# encoder.net
KiCad netlist of a schematic drawn in Altium Designer
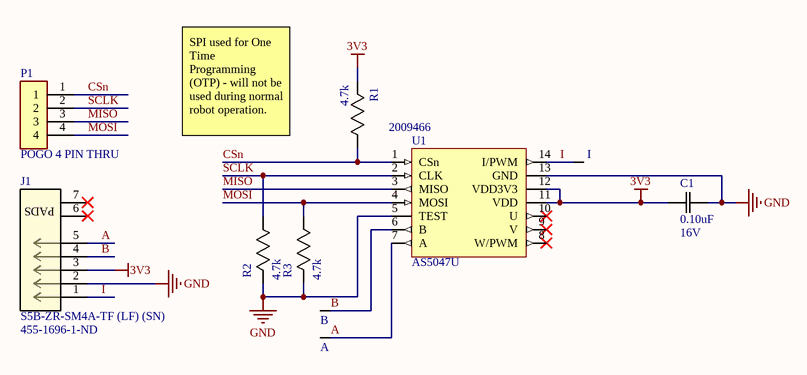
[diagram p0: encoder.SchDoc]

(export (version "E")
  (design (tool "Eeschema 10.0.6"))
  (components
    (comp (ref "A")
      (value "Test Point (Via)")
      (footprint "TP")
      (libsource (lib "AltiumLibraries") (part "Test Point (Via)"))
    )
    (comp (ref "B")
      (value "Test Point (Via)")
      (footprint "TP")
      (libsource (lib "AltiumLibraries") (part "Test Point (Via)"))
    )
    (comp (ref "C1")
      (value "0.10uF")
      (footprint "0603")
      (description "CAP CER 0.10UF 16V X5R 0603/0805")
      (fields (field (name "TOLERANCE") "10%") (field (name "RATING") "16V"))
      (libsource (lib "AltiumLibraries") (part "CAP 0.10uF 16V"))
    )
    (comp (ref "I")
      (value "Test Point (Via)")
      (footprint "TP")
      (libsource (lib "AltiumLibraries") (part "Test Point (Via)"))
    )
    (comp (ref "J1")
      (value "S5B-ZR-SM4A-TF (LF) (SN)")
      (footprint "JST_S5B-ZR-SM4A-TF")
      (description "Connector Header Surface Mount, Right Angle 5 position 0.059\" (1.50mm)")
      (fields
        (field (name "SUPPLIER PART NUMBER 1") "455-1696-1-ND")
        (field (name "COPYRIGHT") "Copyright (C) 2021 Ultra Librarian. All rights reserved.")
      )
      (libsource (lib "AltiumLibraries") (part "CN 5POS JST ZR RA"))
    )
    (comp (ref "P1")
      (value "POGO 4 PIN THRU")
      (footprint "POGO 4 PIN THRU")
      (description "4 pin POGO Holes 0.100\" Pitch")
      (libsource (lib "AltiumLibraries") (part "POGO 4 PIN THRU"))
    )
    (comp (ref "R1")
      (value "4.7k")
      (footprint "0603")
      (description "RES SMD 4.7k OHM 5% 1/8W 0805")
      (fields (field (name "TOLERANCE") "5%"))
      (libsource (lib "AltiumLibraries") (part "RES 4.7k 1/8W - 5%"))
    )
    (comp (ref "R2")
      (value "4.7k")
      (footprint "0603")
      (description "RES SMD 4.7k OHM 5% 1/8W 0805")
      (fields (field (name "TOLERANCE") "5%"))
      (libsource (lib "AltiumLibraries") (part "RES 4.7k 1/8W - 5%"))
    )
    (comp (ref "R3")
      (value "4.7k")
      (footprint "0603")
      (description "RES SMD 4.7k OHM 5% 1/8W 0805")
      (fields (field (name "TOLERANCE") "5%"))
      (libsource (lib "") (part "RES 4.7k 1/8W - 5%_1"))
    )
    (comp (ref "U1")
      (value "AS5047U")
      (footprint "AS5047U")
      (description "14-Bit On-Axis Magnetic Rotary Position Sensor with Up to 14-Bit Binary Incremental Pulse Count")
      (fields (field (name "SUPPLIER PART NUMBER 1") "2009466"))
      (libsource (lib "AltiumLibraries") (part "AS5047U"))
    )
  )
  (nets
    (net (code "1") (name "/A") (class "Default")
      (node (ref "A") (pin "1") (pinfunction "1_1") (pintype "passive"))
      (node (ref "J1") (pin "5") (pinfunction "5_5") (pintype "passive"))
      (node (ref "U1") (pin "7") (pinfunction "A_7") (pintype "output"))
    )
    (net (code "2") (name "/B") (class "Default")
      (node (ref "B") (pin "1") (pinfunction "1_1") (pintype "passive"))
      (node (ref "J1") (pin "4") (pinfunction "4_4") (pintype "passive"))
      (node (ref "U1") (pin "6") (pinfunction "B_6") (pintype "output"))
    )
    (net (code "3") (name "/CSn") (class "Default")
      (node (ref "P1") (pin "1") (pinfunction "1_1") (pintype "passive"))
      (node (ref "R1") (pin "1") (pinfunction "R1_1") (pintype "passive"))
      (node (ref "U1") (pin "1") (pinfunction "CSn_1") (pintype "input"))
    )
    (net (code "4") (name "/I") (class "Default")
      (node (ref "I") (pin "1") (pinfunction "1_1") (pintype "passive"))
      (node (ref "J1") (pin "1") (pinfunction "1_1") (pintype "passive"))
      (node (ref "U1") (pin "14") (pinfunction "I/PWM_14") (pintype "output"))
    )
    (net (code "5") (name "/MISO") (class "Default")
      (node (ref "P1") (pin "3") (pinfunction "3_3") (pintype "passive"))
      (node (ref "U1") (pin "3") (pinfunction "MISO_3") (pintype "output"))
    )
    (net (code "6") (name "/MOSI") (class "Default")
      (node (ref "P1") (pin "4") (pinfunction "4_4") (pintype "passive"))
      (node (ref "R3") (pin "1") (pinfunction "R1_1") (pintype "passive"))
      (node (ref "U1") (pin "4") (pinfunction "MOSI_4") (pintype "input"))
    )
    (net (code "7") (name "/SCLK") (class "Default")
      (node (ref "P1") (pin "2") (pinfunction "2_2") (pintype "passive"))
      (node (ref "R2") (pin "1") (pinfunction "R1_1") (pintype "passive"))
      (node (ref "U1") (pin "2") (pinfunction "CLK_2") (pintype "input"))
    )
    (net (code "8") (name "3V3") (class "Default")
      (node (ref "C1") (pin "1") (pinfunction "C1_1") (pintype "passive"))
      (node (ref "J1") (pin "3") (pinfunction "3_3") (pintype "passive"))
      (node (ref "R1") (pin "2") (pinfunction "R2_2") (pintype "passive"))
      (node (ref "U1") (pin "11") (pinfunction "VDD_11") (pintype "passive"))
      (node (ref "U1") (pin "12") (pinfunction "VDD3V3_12") (pintype "passive"))
    )
    (net (code "9") (name "GND") (class "Default")
      (node (ref "C1") (pin "2") (pinfunction "C2_2") (pintype "passive"))
      (node (ref "J1") (pin "2") (pinfunction "2_2") (pintype "passive"))
      (node (ref "R2") (pin "2") (pinfunction "R2_2") (pintype "passive"))
      (node (ref "R3") (pin "2") (pinfunction "R2_2") (pintype "passive"))
      (node (ref "U1") (pin "13") (pinfunction "GND_13") (pintype "passive"))
      (node (ref "U1") (pin "5") (pinfunction "TEST_5") (pintype "passive"))
    )
    (net (code "10") (name "unconnected-(J1-Pad6)") (class "Default")
      (node (ref "J1") (pin "6") (pinfunction "6_6") (pintype "passive+no_connect"))
    )
    (net (code "11") (name "unconnected-(J1-Pad7)") (class "Default")
      (node (ref "J1") (pin "7") (pinfunction "7_7") (pintype "passive+no_connect"))
    )
    (net (code "12") (name "unconnected-(U1-U-Pad10)") (class "Default")
      (node (ref "U1") (pin "10") (pinfunction "U_10") (pintype "output+no_connect"))
    )
    (net (code "13") (name "unconnected-(U1-V-Pad9)") (class "Default")
      (node (ref "U1") (pin "9") (pinfunction "V_9") (pintype "output+no_connect"))
    )
    (net (code "14") (name "unconnected-(U1-W{slash}PWM-Pad8)") (class "Default")
      (node (ref "U1") (pin "8") (pinfunction "W/PWM_8") (pintype "output+no_connect"))
    )
  )
)
